# Gavrilov1.net
KiCad netlist of a schematic drawn in Altium Designer
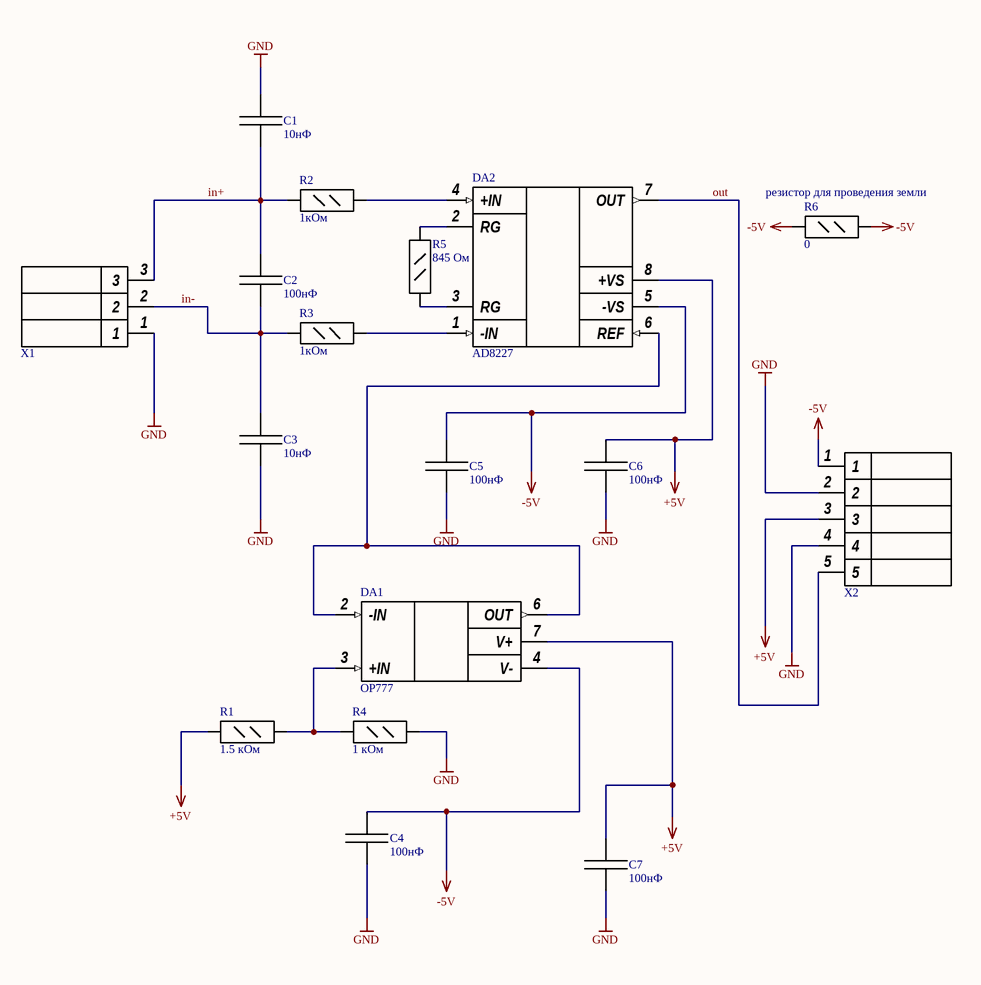
[diagram p0: Gavrilov1.SchDoc]

(export (version "E")
  (design (tool "Eeschema 10.0.6"))
  (components
    (comp (ref "C1")
      (value "10нФ")
      (footprint "CAPC2012L-С0805")
      (description "планарный конденсатор")
      (libsource (lib "NEW-MODUL") (part "C0805"))
    )
    (comp (ref "C2")
      (value "100нФ")
      (footprint "CAPC2012L-С0805")
      (description "планарный конденсатор")
      (libsource (lib "NEW-MODUL") (part "C0805"))
    )
    (comp (ref "C3")
      (value "10нФ")
      (footprint "CAPC2012L-С0805")
      (description "планарный конденсатор")
      (libsource (lib "NEW-MODUL") (part "C0805"))
    )
    (comp (ref "C4")
      (value "100нФ")
      (footprint "CAPC2012L-С0805")
      (description "планарный конденсатор")
      (libsource (lib "NEW-MODUL") (part "C0805"))
    )
    (comp (ref "C5")
      (value "100нФ")
      (footprint "CAPC2012L-С0805")
      (description "планарный конденсатор")
      (libsource (lib "NEW-MODUL") (part "C0805"))
    )
    (comp (ref "C6")
      (value "100нФ")
      (footprint "CAPC2012L-С0805")
      (description "планарный конденсатор")
      (libsource (lib "NEW-MODUL") (part "C0805"))
    )
    (comp (ref "C7")
      (value "100нФ")
      (footprint "CAPC2012L-С0805")
      (description "планарный конденсатор")
      (libsource (lib "NEW-MODUL") (part "C0805"))
    )
    (comp (ref "DA1")
      (value "OP777")
      (footprint "SOIC127P600-8BM")
      (description "Precision Micropower  Single-Supply Operational Amplifiers")
      (libsource (lib "NEW-MODUL") (part "OP777"))
    )
    (comp (ref "DA2")
      (value "AD8227")
      (footprint "SO-8_L")
      (description "instrumentation amplifier")
      (libsource (lib "NEW-MODUL") (part "AD8227"))
    )
    (comp (ref "R1")
      (value "1.5 кОм")
      (footprint "RESC2012N")
      (description "планарный резистор")
      (libsource (lib "NEW-MODUL") (part "R0805"))
    )
    (comp (ref "R2")
      (value "1кОм")
      (footprint "RESC2012N")
      (description "планарный резистор")
      (libsource (lib "NEW-MODUL") (part "R0805"))
    )
    (comp (ref "R3")
      (value "1кОм")
      (footprint "RESC2012N")
      (description "планарный резистор")
      (libsource (lib "NEW-MODUL") (part "R0805"))
    )
    (comp (ref "R4")
      (value "1 кОм")
      (footprint "RESC2012N")
      (description "планарный резистор")
      (libsource (lib "NEW-MODUL") (part "R0805"))
    )
    (comp (ref "R5")
      (value "845 Ом")
      (footprint "RESC2012N")
      (description "планарный резистор")
      (libsource (lib "NEW-MODUL") (part "R0805"))
    )
    (comp (ref "R6")
      (value "0")
      (footprint "RESC2012N")
      (description "планарный резистор")
      (libsource (lib "NEW-MODUL") (part "R0805"))
    )
    (comp (ref "X1") (value "KLEMMNIK3") (footprint "KL3") (libsource (lib "2018-LIB") (part "KLEMMNIK3")))
    (comp (ref "X2")
      (value "KLEMMNIK5")
      (footprint "KLEMNIK5")
      (libsource (lib "2018-LIB") (part "KLEMMNIK5"))
    )
  )
  (nets
    (net (code "1") (name "+5V") (class "Default")
      (node (ref "C6") (pin "2") (pinfunction "2_2") (pintype "passive"))
      (node (ref "C7") (pin "2") (pinfunction "2_2") (pintype "passive"))
      (node (ref "DA1") (pin "7") (pinfunction "V+_7") (pintype "power_in"))
      (node (ref "DA2") (pin "8") (pinfunction "+VS_8") (pintype "power_in"))
      (node (ref "R1") (pin "1") (pinfunction "1_1") (pintype "passive"))
      (node (ref "X2") (pin "3") (pinfunction "3_3") (pintype "passive"))
    )
    (net (code "2") (name "-5V") (class "Default")
      (node (ref "C4") (pin "2") (pinfunction "2_2") (pintype "passive"))
      (node (ref "C5") (pin "2") (pinfunction "2_2") (pintype "passive"))
      (node (ref "DA1") (pin "4") (pinfunction "V-_4") (pintype "power_in"))
      (node (ref "DA2") (pin "5") (pinfunction "-VS_5") (pintype "power_in"))
      (node (ref "R6") (pin "1") (pinfunction "1_1") (pintype "passive"))
      (node (ref "R6") (pin "2") (pinfunction "2_2") (pintype "passive"))
      (node (ref "X2") (pin "1") (pinfunction "1_1") (pintype "passive"))
    )
    (net (code "3") (name "/in+") (class "Default")
      (node (ref "C1") (pin "1") (pinfunction "1_1") (pintype "passive"))
      (node (ref "C2") (pin "2") (pinfunction "2_2") (pintype "passive"))
      (node (ref "R2") (pin "1") (pinfunction "1_1") (pintype "passive"))
      (node (ref "X1") (pin "3") (pinfunction "3_3") (pintype "passive"))
    )
    (net (code "4") (name "/in-") (class "Default")
      (node (ref "C2") (pin "1") (pinfunction "1_1") (pintype "passive"))
      (node (ref "C3") (pin "2") (pinfunction "2_2") (pintype "passive"))
      (node (ref "R3") (pin "1") (pinfunction "1_1") (pintype "passive"))
      (node (ref "X1") (pin "2") (pinfunction "2_2") (pintype "passive"))
    )
    (net (code "5") (name "/out") (class "Default")
      (node (ref "DA2") (pin "7") (pinfunction "OUT_7") (pintype "output"))
      (node (ref "X2") (pin "5") (pinfunction "5_5") (pintype "passive"))
    )
    (net (code "6") (name "GND") (class "Default")
      (node (ref "C1") (pin "2") (pinfunction "2_2") (pintype "passive"))
      (node (ref "C3") (pin "1") (pinfunction "1_1") (pintype "passive"))
      (node (ref "C4") (pin "1") (pinfunction "1_1") (pintype "passive"))
      (node (ref "C5") (pin "1") (pinfunction "1_1") (pintype "passive"))
      (node (ref "C6") (pin "1") (pinfunction "1_1") (pintype "passive"))
      (node (ref "C7") (pin "1") (pinfunction "1_1") (pintype "passive"))
      (node (ref "R4") (pin "2") (pinfunction "2_2") (pintype "passive"))
      (node (ref "X1") (pin "1") (pinfunction "1_1") (pintype "passive"))
      (node (ref "X2") (pin "2") (pinfunction "2_2") (pintype "passive"))
      (node (ref "X2") (pin "4") (pinfunction "4_4") (pintype "passive"))
    )
    (net (code "7") (name "Net-(DA1-+IN)") (class "Default")
      (node (ref "DA1") (pin "3") (pinfunction "+IN_3") (pintype "input"))
      (node (ref "R1") (pin "2") (pinfunction "2_2") (pintype "passive"))
      (node (ref "R4") (pin "1") (pinfunction "1_1") (pintype "passive"))
    )
    (net (code "8") (name "Net-(DA1--IN)") (class "Default")
      (node (ref "DA1") (pin "2") (pinfunction "-IN_2") (pintype "input"))
      (node (ref "DA1") (pin "6") (pinfunction "OUT_6") (pintype "output"))
      (node (ref "DA2") (pin "6") (pinfunction "REF_6") (pintype "input"))
    )
    (net (code "9") (name "Net-(DA2-+IN)") (class "Default")
      (node (ref "DA2") (pin "4") (pinfunction "+IN_4") (pintype "input"))
      (node (ref "R2") (pin "2") (pinfunction "2_2") (pintype "passive"))
    )
    (net (code "10") (name "Net-(DA2--IN)") (class "Default")
      (node (ref "DA2") (pin "1") (pinfunction "-IN_1") (pintype "input"))
      (node (ref "R3") (pin "2") (pinfunction "2_2") (pintype "passive"))
    )
    (net (code "11") (name "Net-(DA2-RG-Pad2)") (class "Default")
      (node (ref "DA2") (pin "2") (pinfunction "RG_2") (pintype "passive"))
      (node (ref "R5") (pin "2") (pinfunction "2_2") (pintype "passive"))
    )
    (net (code "12") (name "Net-(DA2-RG-Pad3)") (class "Default")
      (node (ref "DA2") (pin "3") (pinfunction "RG_3") (pintype "passive"))
      (node (ref "R5") (pin "1") (pinfunction "1_1") (pintype "passive"))
    )
  )
)
